# Connectors.net
KiCad netlist of a schematic drawn in Altium Designer
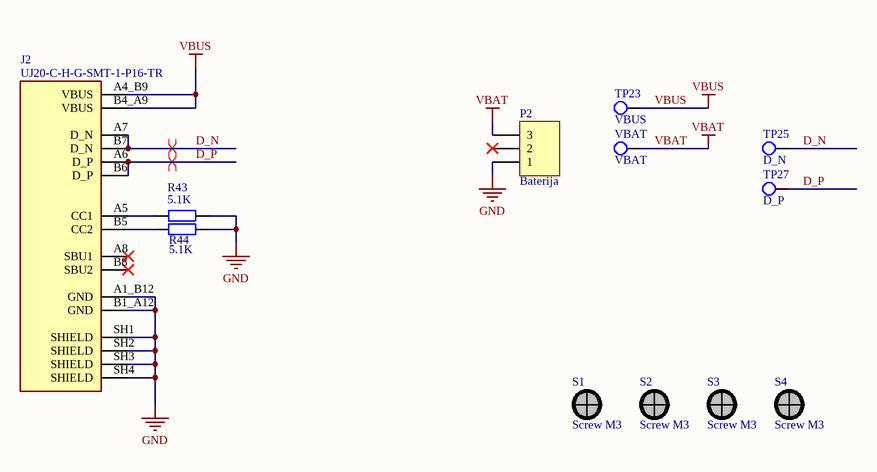
[diagram p0: Connectors.SchDoc]

(export (version "E")
  (design (tool "Eeschema 10.0.6"))
  (components
    (comp (ref "J2")
      (value "UJ20-C-H-G-SMT-1-P16-TR")
      (footprint "SAMESKY_UJ20-C-H-G-SMT-1-P16-TR")
      (fields (field (name "MF") "Same Sky"))
      (libsource (lib "Schematic_library") (part "UJ20-C-H-G-SMT-1-P16-TR"))
    )
    (comp (ref "P2")
      (value "Baterija")
      (footprint "S3B-XH-A-1(LF)(SN)")
      (description "S3B-XH-A-1(LF)(SN)")
      (fields (field (name "PUBLISHER") "Altium Limited"))
      (libsource (lib "Miscellaneous Connectors") (part "Header 3"))
    )
    (comp (ref "R43")
      (value "5.1K")
      (footprint "SMD-0402-RES")
      (description "Resistor")
      (fields (field (name "PUBLISHER") "Altium Limited"))
      (libsource (lib "Miscellaneous Devices") (part "Res2"))
    )
    (comp (ref "R44")
      (value "5.1K")
      (footprint "SMD-0402-RES")
      (description "Resistor")
      (fields (field (name "PUBLISHER") "Altium Limited"))
      (libsource (lib "Miscellaneous Devices") (part "Res2"))
    )
    (comp (ref "S1")
      (value "Screw M3")
      (footprint "M3")
      (libsource (lib "Schematic_library") (part "Screw M3"))
    )
    (comp (ref "S2")
      (value "Screw M3")
      (footprint "M3")
      (libsource (lib "Schematic_library") (part "Screw M3"))
    )
    (comp (ref "S3")
      (value "Screw M3")
      (footprint "M3")
      (libsource (lib "Schematic_library") (part "Screw M3"))
    )
    (comp (ref "S4")
      (value "Screw M3")
      (footprint "M3")
      (libsource (lib "Schematic_library") (part "Screw M3"))
    )
    (comp (ref "TP23")
      (value "VBUS")
      (footprint "testpoint 1 mm")
      (libsource (lib "Schematic_library") (part "testpoint"))
    )
    (comp (ref "TP25")
      (value "D_N")
      (footprint "testpoint 1 mm")
      (libsource (lib "Schematic_library") (part "testpoint"))
    )
    (comp (ref "TP27")
      (value "D_P")
      (footprint "testpoint 1 mm")
      (libsource (lib "Schematic_library") (part "testpoint"))
    )
    (comp (ref "VBAT")
      (value "VBAT")
      (footprint "testpoint 1 mm")
      (libsource (lib "Schematic_library") (part "testpoint"))
    )
  )
  (nets
    (net (code "1") (name "/D_N") (class "Default")
      (node (ref "J2") (pin "A7") (pinfunction "D_N_A7") (pintype "passive"))
      (node (ref "J2") (pin "B7") (pinfunction "D_N_B7") (pintype "passive"))
      (node (ref "TP25") (pin "1") (pinfunction "1_1") (pintype "passive"))
    )
    (net (code "2") (name "/D_P") (class "Default")
      (node (ref "J2") (pin "A6") (pinfunction "D_P_A6") (pintype "passive"))
      (node (ref "J2") (pin "B6") (pinfunction "D_P_B6") (pintype "passive"))
      (node (ref "TP27") (pin "1") (pinfunction "1_1") (pintype "passive"))
    )
    (net (code "3") (name "GND") (class "Default")
      (node (ref "J2") (pin "A1_B12") (pinfunction "GND_A1_B12") (pintype "passive"))
      (node (ref "J2") (pin "B1_A12") (pinfunction "GND_B1_A12") (pintype "passive"))
      (node (ref "J2") (pin "SH1") (pinfunction "SHIELD_SH1") (pintype "passive"))
      (node (ref "J2") (pin "SH2") (pinfunction "SHIELD_SH2") (pintype "passive"))
      (node (ref "J2") (pin "SH3") (pinfunction "SHIELD_SH3") (pintype "passive"))
      (node (ref "J2") (pin "SH4") (pinfunction "SHIELD_SH4") (pintype "passive"))
      (node (ref "P2") (pin "1") (pinfunction "1_1") (pintype "passive"))
      (node (ref "R43") (pin "1") (pinfunction "1_1") (pintype "passive"))
      (node (ref "R44") (pin "1") (pinfunction "1_1") (pintype "passive"))
    )
    (net (code "4") (name "Net-(J2-CC1)") (class "Default")
      (node (ref "J2") (pin "A5") (pinfunction "CC1_A5") (pintype "passive"))
      (node (ref "R43") (pin "2") (pinfunction "2_2") (pintype "passive"))
    )
    (net (code "5") (name "Net-(J2-CC2)") (class "Default")
      (node (ref "J2") (pin "B5") (pinfunction "CC2_B5") (pintype "passive"))
      (node (ref "R44") (pin "2") (pinfunction "2_2") (pintype "passive"))
    )
    (net (code "6") (name "VBAT") (class "Default")
      (node (ref "P2") (pin "3") (pinfunction "3_3") (pintype "passive"))
      (node (ref "VBAT") (pin "1") (pinfunction "1_1") (pintype "passive"))
    )
    (net (code "7") (name "VBUS") (class "Default")
      (node (ref "J2") (pin "A4_B9") (pinfunction "VBUS_A4_B9") (pintype "passive"))
      (node (ref "J2") (pin "B4_A9") (pinfunction "VBUS_B4_A9") (pintype "passive"))
      (node (ref "TP23") (pin "1") (pinfunction "1_1") (pintype "passive"))
    )
    (net (code "8") (name "unconnected-(J2-SBU1-PadA8)") (class "Default")
      (node (ref "J2") (pin "A8") (pinfunction "SBU1_A8") (pintype "passive+no_connect"))
    )
    (net (code "9") (name "unconnected-(J2-SBU2-PadB8)") (class "Default")
      (node (ref "J2") (pin "B8") (pinfunction "SBU2_B8") (pintype "passive+no_connect"))
    )
    (net (code "10") (name "unconnected-(P2-Pad2)") (class "Default")
      (node (ref "P2") (pin "2") (pinfunction "2_2") (pintype "passive+no_connect"))
    )
  )
)
